# LowFreqSignal.net
KiCad netlist of a schematic drawn in Altium Designer
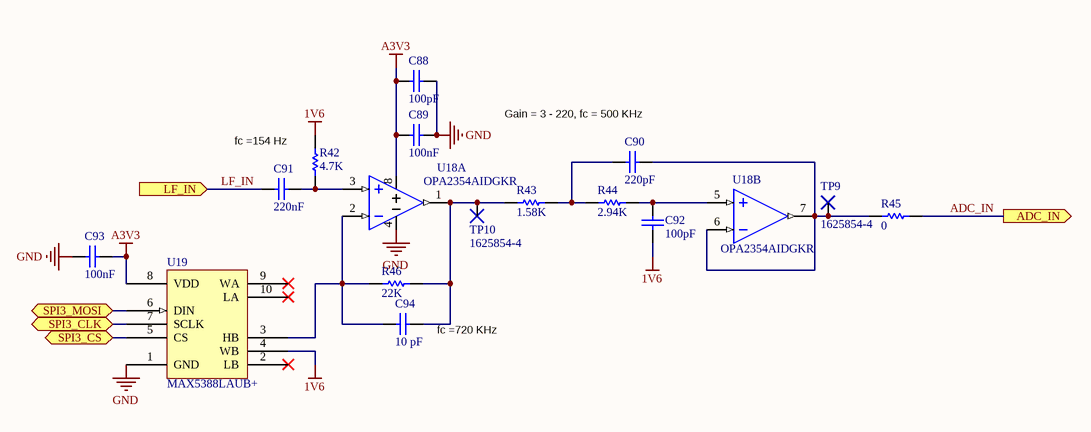
[diagram p0: LowFreqSignal.SchDoc]

(export (version "E")
  (design (tool "Eeschema 10.0.6"))
  (components
    (comp (ref "C88")
      (value "100pF")
      (footprint "0603 Cap")
      (description "CAP CER 100PF 50V X7R 0603")
      (fields
        (field (name "MANUFACTURER") "Samsung Electro-Mechanics America, Inc.")
        (field (name "MANUFACTURER PART NUMBER") "CL10B101KB8NNNC")
      )
      (libsource (lib "Componentes_base") (part "CL10B101KB8NNNC"))
    )
    (comp (ref "C89")
      (value "100nF")
      (footprint "0603 Cap")
      (description "CAP CER 0.1UF 16V X7R 0603")
      (fields
        (field (name "MANUFACTURER") "KEMET")
        (field (name "MANUFACTURER PART NUMBER") "C0603C104K4RACTU")
      )
      (libsource (lib "Componentes_base") (part "C0603C104K4RACTU"))
    )
    (comp (ref "C90")
      (value "220pF")
      (footprint "0603 Cap")
      (description "CAP CER 220PF 50V X7R 0603")
      (fields
        (field (name "MANUFACTURER") "Samsung Electro-Mechanics America, Inc.")
        (field (name "MANUFACTURER PART NUMBER") "CL10B221KB8WPNC")
      )
      (libsource (lib "Componentes_base") (part "CL10B221KB8WPNC"))
    )
    (comp (ref "C91")
      (value "220nF")
      (footprint "0603 Cap")
      (description "CAP CER 0.22UF 16V X7R 0603")
      (fields
        (field (name "MANUFACTURER") "TDK Corporation")
        (field (name "MANUFACTURER PART NUMBER") "C1608X7R1C224K080AC")
      )
      (libsource (lib "Componentes_base") (part "C1608X7R1C224K080AC"))
    )
    (comp (ref "C92")
      (value "100pF")
      (footprint "0603 Cap")
      (description "CAP CER 100PF 50V X7R 0603")
      (fields
        (field (name "MANUFACTURER") "Samsung Electro-Mechanics America, Inc.")
        (field (name "MANUFACTURER PART NUMBER") "CL10B101KB8NNNC")
      )
      (libsource (lib "Componentes_base") (part "CL10B101KB8NNNC"))
    )
    (comp (ref "C93")
      (value "100nF")
      (footprint "0603 Cap")
      (description "CAP CER 0.1UF 16V X7R 0603")
      (fields
        (field (name "MANUFACTURER") "KEMET")
        (field (name "MANUFACTURER PART NUMBER") "C0603C104K4RACTU")
      )
      (libsource (lib "Componentes_base") (part "C0603C104K4RACTU"))
    )
    (comp (ref "C94")
      (value "10 pF")
      (footprint "CAPC1005X05L")
      (description "CAP CER 10PF 50V 5% NP0 0402")
      (fields
        (field (name "MANUFACTURER") "Samsung Electro-Mechanics America, Inc")
        (field (name "MANUFACTURER PART NUMBER") "CL05C100JB5NNNC")
      )
      (libsource (lib "Componentes_base") (part "CL05C100JB5NNNC"))
    )
    (comp (ref "R42")
      (value "4.7K")
      (footprint "0603 Res")
      (description "RES SMD 4.7K OHM 1% 1/10W 0603")
      (fields
        (field (name "MANUFACTURER") "Yageo")
        (field (name "MANUFACTURER PART NUMBER") "RC0603FR-074K7L")
      )
      (libsource (lib "Componentes_base") (part "RC0603FR-074K7L"))
    )
    (comp (ref "R43")
      (value "1.58K")
      (footprint "0603 Res")
      (description "RES SMD 1.58K OHM 1% 1/10W 0603")
      (fields
        (field (name "MANUFACTURER") "Yageo")
        (field (name "MANUFACTURER PART NUMBER") "RC0603FR-071K58L")
      )
      (libsource (lib "Componentes_base") (part "RC0603FR-071K58L"))
    )
    (comp (ref "R44")
      (value "2.94K")
      (footprint "0603 Res")
      (description "RES SMD 2.94K OHM 1% 1/10W 0603")
      (fields
        (field (name "MANUFACTURER") "Yageo")
        (field (name "MANUFACTURER PART NUMBER") "RC0603FR-072K94L")
      )
      (libsource (lib "Componentes_base") (part "RC0603FR-072K94L"))
    )
    (comp (ref "R45")
      (value "0")
      (footprint "RESC1005X04L")
      (description "RES 0.0 OHM 1/16W JUMP 0402")
      (fields
        (field (name "MANUFACTURER") "Samsung Electro-Mechanics America, Inc")
        (field (name "MANUFACTURER PART NUMBER") "RC1005J000CS")
      )
      (libsource (lib "Componentes_base") (part "RC1005J000CS"))
    )
    (comp (ref "R46")
      (value "22K")
      (footprint "0603 Res")
      (description "RES SMD 22K OHM 1% 1/10W 0603")
      (fields
        (field (name "MANUFACTURER") "Yageo")
        (field (name "MANUFACTURER PART NUMBER") "RC0603FR-0722KL")
      )
      (libsource (lib "Componentes_base") (part "RC0603FR-0722KL"))
    )
    (comp (ref "TP9")
      (value "1625854-4")
      (footprint "TESTPOINT 1206")
      (description "1206 PROBE PAD")
      (fields (field (name "MANUFACTURER") "TE Connectivity AMP Connectors"))
      (libsource (lib "Componentes_base") (part "1625854-4"))
    )
    (comp (ref "TP10")
      (value "1625854-4")
      (footprint "TESTPOINT 1206")
      (description "1206 PROBE PAD")
      (fields (field (name "MANUFACTURER") "TE Connectivity AMP Connectors"))
      (libsource (lib "Componentes_base") (part "1625854-4"))
    )
    (comp (ref "U18")
      (value "OPA2354AIDGKR")
      (footprint "MSOP-8")
      (description "IC OPAMP VFB 100MHZ RRO 8VSSOP")
      (fields (field (name "MANUFACTURER") "Texas Instruments"))
      (libsource (lib "Componentes_base") (part "OPA2354AIDGKR"))
    )
    (comp (ref "U19")
      (value "MAX5388LAUB+")
      (footprint "uSOP-10 uMAX")
      (description "IC DGTL POT 256POS 10K 10UMAX")
      (fields (field (name "MANUFACTURER") "Maxim Integrated") (field (name "TOLERANCE") "±25%"))
      (libsource (lib "Componentes_base") (part "MAX5388LAUB+"))
    )
  )
  (nets
    (net (code "1") (name "/ADC_IN") (class "Default")
      (node (ref "R45") (pin "2") (pinfunction "2_2") (pintype "passive"))
    )
    (net (code "2") (name "/LF_IN") (class "Default")
      (node (ref "C91") (pin "1") (pinfunction "1_1") (pintype "passive"))
    )
    (net (code "3") (name "/SPI3_CLK") (class "Default")
      (node (ref "U19") (pin "7") (pinfunction "SCLK_7") (pintype "passive"))
    )
    (net (code "4") (name "/SPI3_CS") (class "Default")
      (node (ref "U19") (pin "5") (pinfunction "CS_5") (pintype "passive"))
    )
    (net (code "5") (name "/SPI3_MOSI") (class "Default")
      (node (ref "U19") (pin "6") (pinfunction "DIN_6") (pintype "input"))
    )
    (net (code "6") (name "1V6") (class "Default")
      (node (ref "C92") (pin "1") (pinfunction "1_1") (pintype "passive"))
      (node (ref "R42") (pin "2") (pinfunction "2_2") (pintype "passive"))
      (node (ref "U19") (pin "4") (pinfunction "WB_4") (pintype "passive"))
    )
    (net (code "7") (name "A3V3") (class "Default")
      (node (ref "C88") (pin "1") (pinfunction "1_1") (pintype "passive"))
      (node (ref "C89") (pin "1") (pinfunction "1_1") (pintype "passive"))
      (node (ref "C93") (pin "2") (pinfunction "2_2") (pintype "passive"))
      (node (ref "U18") (pin "8") (pinfunction "V+_8") (pintype "power_in"))
      (node (ref "U19") (pin "8") (pinfunction "VDD_8") (pintype "power_in"))
    )
    (net (code "8") (name "GND") (class "Default")
      (node (ref "C88") (pin "2") (pinfunction "2_2") (pintype "passive"))
      (node (ref "C89") (pin "2") (pinfunction "2_2") (pintype "passive"))
      (node (ref "C93") (pin "1") (pinfunction "1_1") (pintype "passive"))
      (node (ref "U18") (pin "4") (pinfunction "V-_4") (pintype "power_in"))
      (node (ref "U19") (pin "1") (pinfunction "GND_1") (pintype "power_in"))
    )
    (net (code "9") (name "Net-(C90-Pad2)") (class "Default")
      (node (ref "C90") (pin "2") (pinfunction "2_2") (pintype "passive"))
      (node (ref "R43") (pin "2") (pinfunction "2_2") (pintype "passive"))
      (node (ref "R44") (pin "1") (pinfunction "1_1") (pintype "passive"))
    )
    (net (code "10") (name "Net-(U18A-IN+A)") (class "Default")
      (node (ref "C91") (pin "2") (pinfunction "2_2") (pintype "passive"))
      (node (ref "R42") (pin "1") (pinfunction "1_1") (pintype "passive"))
      (node (ref "U18") (pin "3") (pinfunction "IN+A_3") (pintype "input"))
    )
    (net (code "11") (name "Net-(U18A-IN-A)") (class "Default")
      (node (ref "C94") (pin "1") (pinfunction "1_1") (pintype "passive"))
      (node (ref "R46") (pin "1") (pinfunction "1_1") (pintype "passive"))
      (node (ref "U18") (pin "2") (pinfunction "IN-A_2") (pintype "input"))
      (node (ref "U19") (pin "3") (pinfunction "HB_3") (pintype "passive"))
    )
    (net (code "12") (name "Net-(U18A-OUTA)") (class "Default")
      (node (ref "C94") (pin "2") (pinfunction "2_2") (pintype "passive"))
      (node (ref "R43") (pin "1") (pinfunction "1_1") (pintype "passive"))
      (node (ref "R46") (pin "2") (pinfunction "2_2") (pintype "passive"))
      (node (ref "TP10") (pin "1") (pinfunction "1_1") (pintype "passive"))
      (node (ref "U18") (pin "1") (pinfunction "OUTA_1") (pintype "output"))
    )
    (net (code "13") (name "Net-(U18B-IN+B)") (class "Default")
      (node (ref "C92") (pin "2") (pinfunction "2_2") (pintype "passive"))
      (node (ref "R44") (pin "2") (pinfunction "2_2") (pintype "passive"))
      (node (ref "U18") (pin "5") (pinfunction "IN+B_5") (pintype "input"))
    )
    (net (code "14") (name "Net-(U18B-IN-B)") (class "Default")
      (node (ref "C90") (pin "1") (pinfunction "1_1") (pintype "passive"))
      (node (ref "R45") (pin "1") (pinfunction "1_1") (pintype "passive"))
      (node (ref "TP9") (pin "1") (pinfunction "1_1") (pintype "passive"))
      (node (ref "U18") (pin "6") (pinfunction "IN-B_6") (pintype "input"))
      (node (ref "U18") (pin "7") (pinfunction "OUTB_7") (pintype "output"))
    )
    (net (code "15") (name "unconnected-(U19-LA-Pad10)") (class "Default")
      (node (ref "U19") (pin "10") (pinfunction "LA_10") (pintype "passive+no_connect"))
    )
    (net (code "16") (name "unconnected-(U19-LB-Pad2)") (class "Default")
      (node (ref "U19") (pin "2") (pinfunction "LB_2") (pintype "passive+no_connect"))
    )
    (net (code "17") (name "unconnected-(U19-WA-Pad9)") (class "Default")
      (node (ref "U19") (pin "9") (pinfunction "WA_9") (pintype "passive+no_connect"))
    )
  )
)
